# shoulderbutton.net
KiCad netlist of a schematic drawn in EAGLE
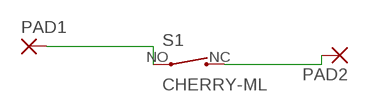
[diagram p0: schematic, sheet 1]

(export (version "E")
  (design (tool "Eeschema 10.0.6"))
  (components
    (comp (ref "PAD1")
      (value "2,15/1,0")
      (footprint "eagle-import:2,15_1,0")
      (libsource (lib "eagle-import") (part "2,15/1,0"))
    )
    (comp (ref "PAD2")
      (value "2,15/1,0")
      (footprint "eagle-import:2,15_1,0")
      (libsource (lib "eagle-import") (part "2,15/1,0"))
    )
    (comp (ref "S1")
      (value "CHERRY-ML")
      (footprint "eagle-import:CHERRY-ML")
      (libsource (lib "eagle-import") (part "CHERRY-ML"))
    )
  )
  (nets
    (net (code "1") (name "Net-(PAD1-P)") (class "Default")
      (node (ref "PAD1") (pin "1") (pinfunction "P_1") (pintype "passive"))
      (node (ref "S1") (pin "NO") (pinfunction "1_NO") (pintype "passive"))
    )
    (net (code "2") (name "Net-(PAD2-P)") (class "Default")
      (node (ref "PAD2") (pin "1") (pinfunction "P_1") (pintype "passive"))
      (node (ref "S1") (pin "NC") (pinfunction "2_NC") (pintype "passive"))
    )
  )
)
